# main_keyring.net
KiCad netlist of a schematic drawn in EAGLE
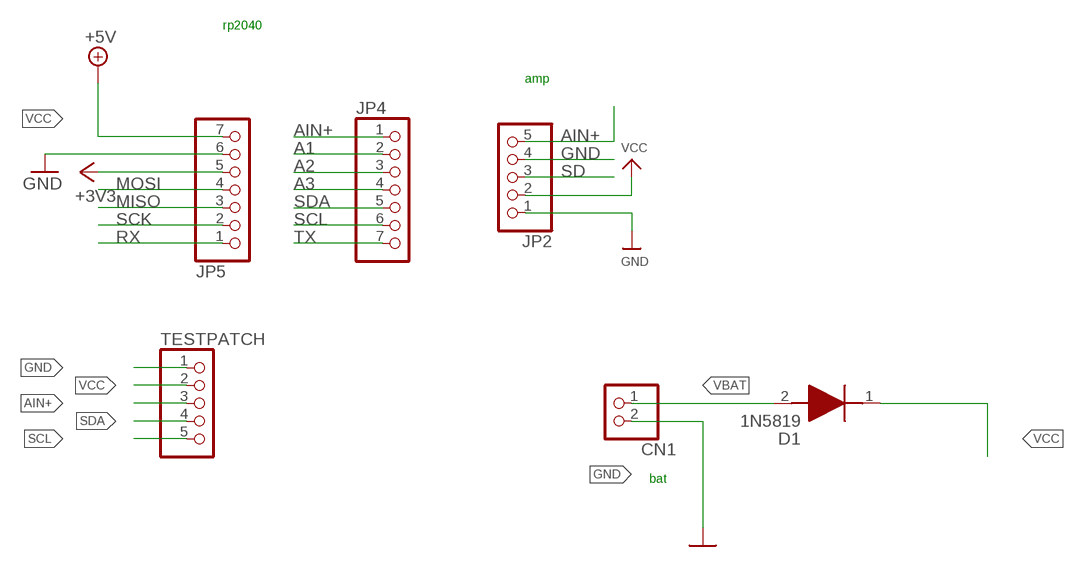
[diagram p0: schematic, sheet 1]

(export (version "E")
  (design (tool "Eeschema 10.0.6"))
  (components
    (comp (ref "CN1")
      (value "JST_2PIN-THM")
      (footprint "eagle-import:JST-PH-2-THM")
      (libsource (lib "eagle-import") (part "JST_2PIN-THM"))
    )
    (comp (ref "D1")
      (value "1N5819")
      (footprint "eagle-import:DIOAD1414W86L464D238")
      (fields (field (name "RS_PART_NUMBER") "4864460P"))
      (libsource (lib "eagle-import") (part "1N5819"))
    )
    (comp (ref "JP2")
      (value "HEADER-1X570MIL")
      (footprint "eagle-import:1X05_ROUND_70")
      (libsource (lib "eagle-import") (part "HEADER-1X570MIL"))
    )
    (comp (ref "JP4")
      (value "HEADER-1X7")
      (footprint "eagle-import:1X07_OVAL")
      (libsource (lib "eagle-import") (part "HEADER-1X7"))
    )
    (comp (ref "JP5")
      (value "HEADER-1X7")
      (footprint "eagle-import:1X07_OVAL")
      (libsource (lib "eagle-import") (part "HEADER-1X7"))
    )
    (comp (ref "TESTPATCH")
      (value "PINHD-1X5")
      (footprint "eagle-import:1X05")
      (libsource (lib "eagle-import") (part "PINHD-1X5"))
    )
  )
  (nets
    (net (code "1") (name "+3V3") (class "Default")
      (node (ref "JP5") (pin "5") (pinfunction "5_5") (pintype "passive"))
    )
    (net (code "2") (name "/A1") (class "Default")
      (node (ref "JP4") (pin "2") (pinfunction "2_2") (pintype "passive"))
    )
    (net (code "3") (name "/A2") (class "Default")
      (node (ref "JP4") (pin "3") (pinfunction "3_3") (pintype "passive"))
    )
    (net (code "4") (name "/A3") (class "Default")
      (node (ref "JP4") (pin "4") (pinfunction "4_4") (pintype "passive"))
    )
    (net (code "5") (name "/MISO") (class "Default")
      (node (ref "JP5") (pin "3") (pinfunction "3_3") (pintype "passive"))
    )
    (net (code "6") (name "/MOSI") (class "Default")
      (node (ref "JP5") (pin "4") (pinfunction "4_4") (pintype "passive"))
    )
    (net (code "7") (name "/RX") (class "Default")
      (node (ref "JP5") (pin "1") (pinfunction "1_1") (pintype "passive"))
    )
    (net (code "8") (name "/SCK") (class "Default")
      (node (ref "JP5") (pin "2") (pinfunction "2_2") (pintype "passive"))
    )
    (net (code "9") (name "/SD") (class "Default")
      (node (ref "JP2") (pin "3") (pinfunction "3_3") (pintype "passive"))
    )
    (net (code "10") (name "/TX") (class "Default")
      (node (ref "JP4") (pin "7") (pinfunction "7_7") (pintype "passive"))
    )
    (net (code "11") (name "AIN+") (class "Default")
      (node (ref "JP2") (pin "5") (pinfunction "5_5") (pintype "passive"))
      (node (ref "JP4") (pin "1") (pinfunction "1_1") (pintype "passive"))
      (node (ref "TESTPATCH") (pin "3") (pinfunction "3_3") (pintype "passive"))
    )
    (net (code "12") (name "GND") (class "Default")
      (node (ref "CN1") (pin "2") (pinfunction "1_2") (pintype "passive"))
      (node (ref "JP2") (pin "1") (pinfunction "1_1") (pintype "passive"))
      (node (ref "JP2") (pin "4") (pinfunction "4_4") (pintype "passive"))
      (node (ref "JP5") (pin "6") (pinfunction "6_6") (pintype "passive"))
      (node (ref "TESTPATCH") (pin "1") (pinfunction "1_1") (pintype "passive"))
    )
    (net (code "13") (name "SCL") (class "Default")
      (node (ref "JP4") (pin "6") (pinfunction "6_6") (pintype "passive"))
      (node (ref "TESTPATCH") (pin "5") (pinfunction "5_5") (pintype "passive"))
    )
    (net (code "14") (name "SDA") (class "Default")
      (node (ref "JP4") (pin "5") (pinfunction "5_5") (pintype "passive"))
      (node (ref "TESTPATCH") (pin "4") (pinfunction "4_4") (pintype "passive"))
    )
    (net (code "15") (name "VBAT") (class "Default")
      (node (ref "CN1") (pin "1") (pinfunction "2_1") (pintype "passive"))
      (node (ref "D1") (pin "2") (pinfunction "A_2") (pintype "bidirectional"))
    )
    (net (code "16") (name "VCC") (class "Default")
      (node (ref "D1") (pin "1") (pinfunction "K_1") (pintype "bidirectional"))
      (node (ref "JP2") (pin "2") (pinfunction "2_2") (pintype "passive"))
      (node (ref "JP5") (pin "7") (pinfunction "7_7") (pintype "passive"))
      (node (ref "TESTPATCH") (pin "2") (pinfunction "2_2") (pintype "passive"))
    )
  )
)
